# Sheet1.net
KiCad netlist of a schematic drawn in Altium Designer
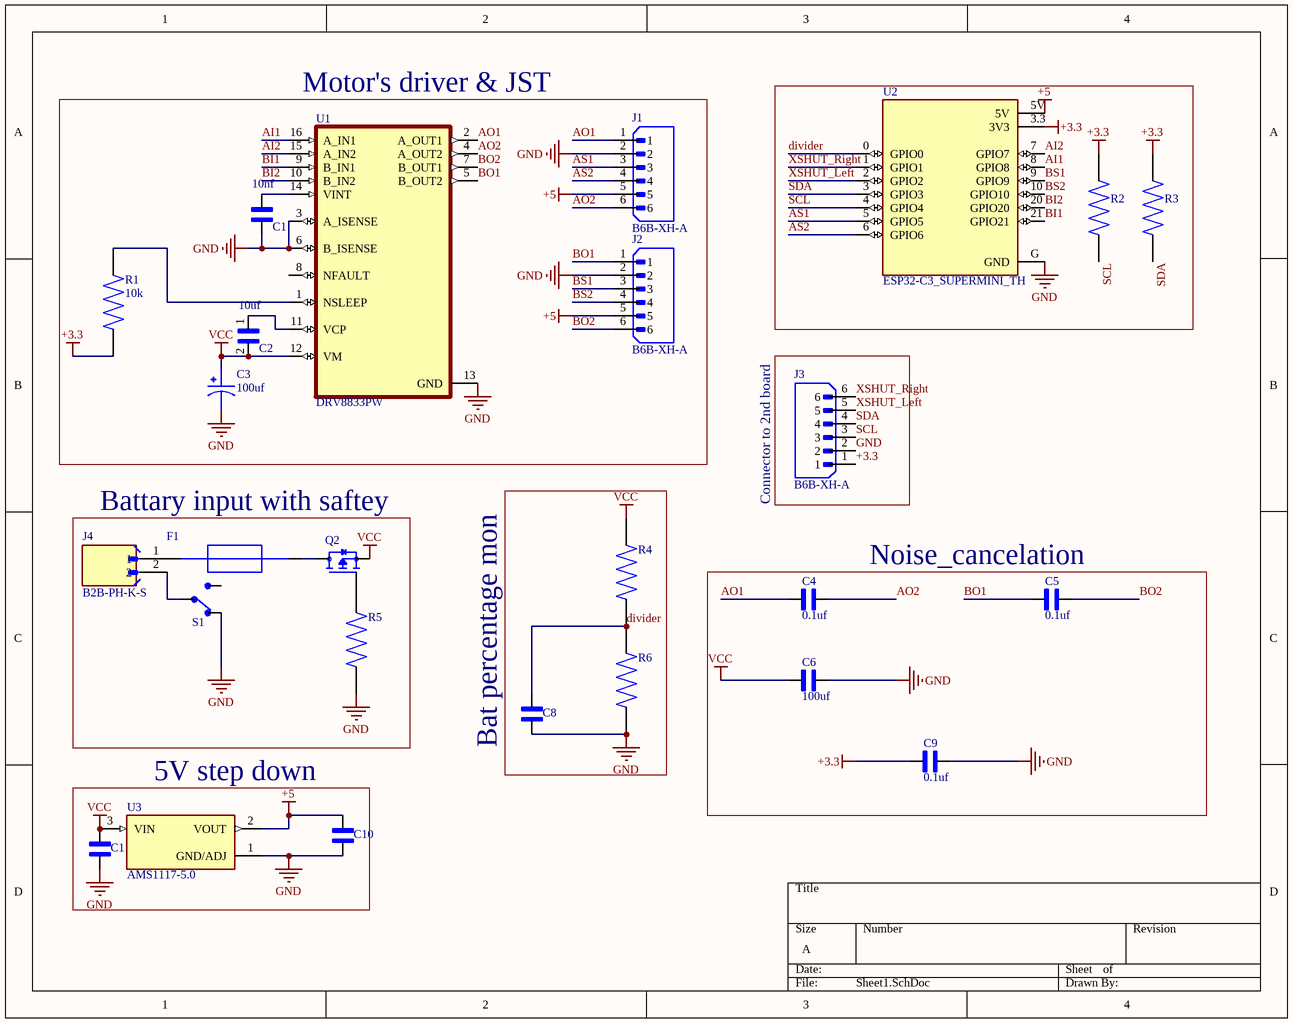
[diagram p0: Sheet1.SchDoc]

(export (version "E")
  (design (tool "Eeschema 10.0.6"))
  (components
    (comp (ref "C1")
      (value "10nf")
      (footprint "CAPC2012X88N")
      (description "0805 X7R ceramic capacitor,47nF 100V ¦ KEMET C0805C473K1RACTU")
      (fields (field (name "MF") "KEMET") (field (name "MP") "C0805C473K1RACTU"))
      (libsource (lib "Schlib1") (part "C0805C473K1RACTU"))
    )
    (comp (ref "C2")
      (value "10uf")
      (footprint "PcbLib1:CAPC3216X180N")
      (description "C Series 1206 10 nF 630 V Â±5 % Tolerance NP0 SMT Multilayer Ceramic Capacitor")
      (fields (field (name "MF") "TDK") (field (name "MP") "C3216NP02J103J160AA"))
      (libsource (lib "Schlib1") (part "C3216NP02J103J160AA"))
    )
    (comp (ref "C3")
      (value "100uf")
      (footprint "CAPMP3216X180N")
      (description "Capacitor;Tantalum;Cap 10uF;Tol 20%;SMT;Vol-Rtg 10V;Code 3216;TR ¦ AVX TAJA106M010RNJ")
      (fields (field (name "MF") "AVX") (field (name "MP") "TAJA106M010RNJ"))
      (libsource (lib "Schlib1") (part "TAJA106M010RNJ"))
    )
    (comp (ref "C4")
      (value "0.1uf")
      (footprint "CAP_ECHU1H181GX5")
      (description "Capacitor Pps Film, 180pf, 50v, 2%, 0805capacitor Pps Film, 180pf, 50v, 2%, 0805")
      (fields (field (name "MF") "Panasonic") (field (name "DIGI-KEY_PART_NUMBER") "PCF1287TR-ND"))
      (libsource (lib "Schlib1") (part "ECHU1H181GX5"))
    )
    (comp (ref "C5")
      (value "0.1uf")
      (footprint "CAP_ECHU1H181GX5")
      (description "Capacitor Pps Film, 180pf, 50v, 2%, 0805capacitor Pps Film, 180pf, 50v, 2%, 0805")
      (fields (field (name "MF") "Panasonic") (field (name "DIGI-KEY_PART_NUMBER") "PCF1287TR-ND"))
      (libsource (lib "Schlib1") (part "ECHU1H181GX5"))
    )
    (comp (ref "C6")
      (value "100uf")
      (footprint "CAPC3225X280N")
      (description "100 ÂµF Â±20% 6.3V Ceramic Capacitor X5R 1210 (3225 Metric)")
      (fields (field (name "MF") "Samsung") (field (name "MP") "CL32A107MQVNNWE"))
      (libsource (lib "Schlib1") (part "CL32A107MQVNNWE"))
    )
    (comp (ref "C8")
      (value "C0805C473K1RACTU")
      (footprint "CAPC2012X88N")
      (description "0805 X7R ceramic capacitor,47nF 100V ¦ KEMET C0805C473K1RACTU")
      (fields (field (name "MF") "KEMET"))
      (libsource (lib "Schlib1") (part "C0805C473K1RACTU"))
    )
    (comp (ref "C9")
      (value "0.1uf")
      (footprint "CAPC3225X280N")
      (description "100 ÂµF Â±20% 6.3V Ceramic Capacitor X5R 1210 (3225 Metric)")
      (fields (field (name "MF") "Samsung") (field (name "MP") "CL32A107MQVNNWE"))
      (libsource (lib "Schlib1") (part "CL32A107MQVNNWE"))
    )
    (comp (ref "C10")
      (value "C0805C473K1RACTU")
      (footprint "CAPC2012X88N")
      (description "0805 X7R ceramic capacitor,47nF 100V ¦ KEMET C0805C473K1RACTU")
      (fields (field (name "MF") "KEMET"))
      (libsource (lib "Schlib1") (part "C0805C473K1RACTU"))
    )
    (comp (ref "C11")
      (value "C0805C473K1RACTU")
      (footprint "CAPC2012X88N")
      (description "0805 X7R ceramic capacitor,47nF 100V ¦ KEMET C0805C473K1RACTU")
      (fields (field (name "MF") "KEMET"))
      (libsource (lib "") (part "C0805C473K1RACTU_1"))
    )
    (comp (ref "F1")
      (value "1206L035YR")
      (footprint "FUSC3216X75N")
      (description "Polymeric PTC Resettable Fuse 6V 350 mA Ih Surface Mount 1206 (3216 Metric), Concave")
      (fields (field (name "MF") "Littelfuse Inc."))
      (libsource (lib "Schlib1") (part "1206L035YR"))
    )
    (comp (ref "J1")
      (value "B6B-XH-A")
      (footprint "JST_B6B-XH-A")
      (fields (field (name "MF") "{'manufacturer': u'JST Sales America Inc.'}"))
      (libsource (lib "Schlib1") (part "B6B-XH-A"))
    )
    (comp (ref "J2")
      (value "B6B-XH-A")
      (footprint "JST_B6B-XH-A")
      (fields (field (name "MF") "{'manufacturer': u'JST Sales America Inc.'}"))
      (libsource (lib "Schlib1") (part "B6B-XH-A"))
    )
    (comp (ref "J3")
      (value "B6B-XH-A")
      (footprint "JST_B6B-XH-A")
      (fields (field (name "MF") "{'manufacturer': u'JST Sales America Inc.'}"))
      (libsource (lib "") (part "B6B-XH-A_1"))
    )
    (comp (ref "J4")
      (value "B2B-PH-K-S")
      (footprint "JST_B2B-PH-K-S")
      (description "Connector Header Through Hole 2 position 0.079 (2.00mm)")
      (fields (field (name "MF") "JST Sales America Inc."))
      (libsource (lib "Schlib1") (part "B2B-PH-K-S"))
    )
    (comp (ref "Q2")
      (value "IRF9540")
      (footprint "TO254P1052X465X1989-3")
      (description "P-Channel 100 V 19A (Tc) 3.7W (Ta), 150W (Tc) Surface Mount DÂ²PAK (TO-263)")
      (fields (field (name "MF") "Vishay"))
      (libsource (lib "Schlib1") (part "IRF9540"))
    )
    (comp (ref "R1")
      (value "10k")
      (footprint "RESC2012X60N")
      (description "Surface Mount Thick Film Resistor, RC Series, 39 ohm, 125 mW, - 5%, 150 V, 0805 [2012 Metric]")
      (fields (field (name "MF") "Yageo") (field (name "MP") "RC0805JR-0739RL"))
      (libsource (lib "Schlib1") (part "RC0805JR-0739RL"))
    )
    (comp (ref "R2")
      (value "RC0805JR-0739RL")
      (footprint "RESC2012X60N")
      (description "Surface Mount Thick Film Resistor, RC Series, 39 ohm, 125 mW, - 5%, 150 V, 0805 [2012 Metric]")
      (fields (field (name "MF") "Yageo"))
      (libsource (lib "Schlib1") (part "RC0805JR-0739RL"))
    )
    (comp (ref "R3")
      (value "RC0805JR-0739RL")
      (footprint "RESC2012X60N")
      (description "Surface Mount Thick Film Resistor, RC Series, 39 ohm, 125 mW, - 5%, 150 V, 0805 [2012 Metric]")
      (fields (field (name "MF") "Yageo"))
      (libsource (lib "Schlib1") (part "RC0805JR-0739RL"))
    )
    (comp (ref "R4")
      (value "RC0805JR-0739RL")
      (footprint "RESC2012X60N")
      (description "Surface Mount Thick Film Resistor, RC Series, 39 ohm, 125 mW, - 5%, 150 V, 0805 [2012 Metric]")
      (fields (field (name "MF") "Yageo"))
      (libsource (lib "Schlib1") (part "RC0805JR-0739RL"))
    )
    (comp (ref "R5")
      (value "RC0805JR-0739RL")
      (footprint "RESC2012X60N")
      (description "Surface Mount Thick Film Resistor, RC Series, 39 ohm, 125 mW, - 5%, 150 V, 0805 [2012 Metric]")
      (fields (field (name "MF") "Yageo"))
      (libsource (lib "Schlib1") (part "RC0805JR-0739RL"))
    )
    (comp (ref "R6")
      (value "RC0805JR-0739RL")
      (footprint "RESC2012X60N")
      (description "Surface Mount Thick Film Resistor, RC Series, 39 ohm, 125 mW, - 5%, 150 V, 0805 [2012 Metric]")
      (fields (field (name "MF") "Yageo"))
      (libsource (lib "Schlib1") (part "RC0805JR-0739RL"))
    )
    (comp (ref "S1")
      (value "1101M2S3CQE2")
      (footprint "SW_1101M2S3CQE2")
      (description "Switch,Slide,Sealed,SPDT,ON-NONE-ON,PC Mnt,.200 Blk Act,6A,120VAC,PC Thru-Hole ¦ C&K 1101M2S3CQE2")
      (fields (field (name "MF") "C&K"))
      (libsource (lib "Schlib1") (part "1101M2S3CQE2"))
    )
    (comp (ref "U1")
      (value "DRV8833PW")
      (footprint "SOP65P640X120-16N")
      (description "10.8-V, 2-A dual H-bridge motor driver with current regulation")
      (fields (field (name "MF") "Texas Instruments"))
      (libsource (lib "Schlib1") (part "DRV8833PW"))
    )
    (comp (ref "U2")
      (value "ESP32-C3_SUPERMINI_TH")
      (footprint "MODULE_ESP32-C3_SUPERMINI_TH")
      (description "Super tiny ESP32-C3 board")
      (fields (field (name "MF") "Espressif Systems") (field (name "MP") "ESP32-C3 SuperMini_TH"))
      (libsource (lib "Schlib1") (part "ESP32-C3_SUPERMINI_TH"))
    )
    (comp (ref "U3")
      (value "AMS1117-5.0")
      (footprint "SOT229P700X180-4N")
      (description "1A LOW DROPOUT VOLTAGE REGULATOR")
      (fields (field (name "MF") "ams"))
      (libsource (lib "Schlib1") (part "AMS1117-5.0"))
    )
  )
  (nets
    (net (code "1") (name "+3.3") (class "Default")
      (node (ref "C9") (pin "1") (pinfunction "1_1") (pintype "passive"))
      (node (ref "J3") (pin "1") (pinfunction "1_1") (pintype "passive"))
      (node (ref "R1") (pin "1") (pinfunction "1_1") (pintype "passive"))
      (node (ref "R2") (pin "1") (pinfunction "1_1") (pintype "passive"))
      (node (ref "R3") (pin "1") (pinfunction "1_1") (pintype "passive"))
      (node (ref "U2") (pin "3.3") (pinfunction "3V3_3.3") (pintype "power_in"))
    )
    (net (code "2") (name "+5") (class "Default")
      (node (ref "C10") (pin "1") (pinfunction "1_1") (pintype "passive"))
      (node (ref "J1") (pin "5") (pinfunction "5_5") (pintype "passive"))
      (node (ref "J2") (pin "5") (pinfunction "5_5") (pintype "passive"))
      (node (ref "U2") (pin "5V") (pinfunction "5V_5V") (pintype "power_in"))
      (node (ref "U3") (pin "2") (pinfunction "VOUT_2") (pintype "output"))
    )
    (net (code "3") (name "/AI1") (class "Default")
      (node (ref "U1") (pin "16") (pinfunction "A_IN1_16") (pintype "input"))
      (node (ref "U2") (pin "8") (pinfunction "GPIO8_8") (pintype "bidirectional"))
    )
    (net (code "4") (name "/AI2") (class "Default")
      (node (ref "U1") (pin "15") (pinfunction "A_IN2_15") (pintype "input"))
      (node (ref "U2") (pin "7") (pinfunction "GPIO7_7") (pintype "bidirectional"))
    )
    (net (code "5") (name "/AO1") (class "Default")
      (node (ref "C4") (pin "2") (pinfunction "2_2") (pintype "passive"))
      (node (ref "J1") (pin "1") (pinfunction "1_1") (pintype "passive"))
      (node (ref "U1") (pin "2") (pinfunction "A_OUT1_2") (pintype "output"))
    )
    (net (code "6") (name "/AO2") (class "Default")
      (node (ref "C4") (pin "1") (pinfunction "1_1") (pintype "passive"))
      (node (ref "J1") (pin "6") (pinfunction "6_6") (pintype "passive"))
      (node (ref "U1") (pin "4") (pinfunction "A_OUT2_4") (pintype "output"))
    )
    (net (code "7") (name "/AS1") (class "Default")
      (node (ref "J1") (pin "3") (pinfunction "3_3") (pintype "passive"))
      (node (ref "U2") (pin "5") (pinfunction "GPIO5_5") (pintype "bidirectional"))
    )
    (net (code "8") (name "/AS2") (class "Default")
      (node (ref "J1") (pin "4") (pinfunction "4_4") (pintype "passive"))
      (node (ref "U2") (pin "6") (pinfunction "GPIO6_6") (pintype "bidirectional"))
    )
    (net (code "9") (name "/BI1") (class "Default")
      (node (ref "U1") (pin "9") (pinfunction "B_IN1_9") (pintype "input"))
      (node (ref "U2") (pin "21") (pinfunction "GPIO21_21") (pintype "bidirectional"))
    )
    (net (code "10") (name "/BI2") (class "Default")
      (node (ref "U1") (pin "10") (pinfunction "B_IN2_10") (pintype "input"))
      (node (ref "U2") (pin "20") (pinfunction "GPIO20_20") (pintype "bidirectional"))
    )
    (net (code "11") (name "/BO1") (class "Default")
      (node (ref "C5") (pin "2") (pinfunction "2_2") (pintype "passive"))
      (node (ref "J2") (pin "1") (pinfunction "1_1") (pintype "passive"))
      (node (ref "U1") (pin "5") (pinfunction "B_OUT2_5") (pintype "output"))
    )
    (net (code "12") (name "/BO2") (class "Default")
      (node (ref "C5") (pin "1") (pinfunction "1_1") (pintype "passive"))
      (node (ref "J2") (pin "6") (pinfunction "6_6") (pintype "passive"))
      (node (ref "U1") (pin "7") (pinfunction "B_OUT1_7") (pintype "output"))
    )
    (net (code "13") (name "/BS1") (class "Default")
      (node (ref "J2") (pin "3") (pinfunction "3_3") (pintype "passive"))
      (node (ref "U2") (pin "9") (pinfunction "GPIO9_9") (pintype "bidirectional"))
    )
    (net (code "14") (name "/BS2") (class "Default")
      (node (ref "J2") (pin "4") (pinfunction "4_4") (pintype "passive"))
      (node (ref "U2") (pin "10") (pinfunction "GPIO10_10") (pintype "bidirectional"))
    )
    (net (code "15") (name "/SCL") (class "Default")
      (node (ref "J3") (pin "3") (pinfunction "3_3") (pintype "passive"))
      (node (ref "R2") (pin "2") (pinfunction "2_2") (pintype "passive"))
      (node (ref "U2") (pin "4") (pinfunction "GPIO4_4") (pintype "bidirectional"))
    )
    (net (code "16") (name "/SDA") (class "Default")
      (node (ref "J3") (pin "4") (pinfunction "4_4") (pintype "passive"))
      (node (ref "R3") (pin "2") (pinfunction "2_2") (pintype "passive"))
      (node (ref "U2") (pin "3") (pinfunction "GPIO3_3") (pintype "bidirectional"))
    )
    (net (code "17") (name "/XSHUT_Left") (class "Default")
      (node (ref "J3") (pin "5") (pinfunction "5_5") (pintype "passive"))
      (node (ref "U2") (pin "2") (pinfunction "GPIO2_2") (pintype "bidirectional"))
    )
    (net (code "18") (name "/XSHUT_Right") (class "Default")
      (node (ref "J3") (pin "6") (pinfunction "6_6") (pintype "passive"))
      (node (ref "U2") (pin "1") (pinfunction "GPIO1_1") (pintype "bidirectional"))
    )
    (net (code "19") (name "/divider") (class "Default")
      (node (ref "C8") (pin "1") (pinfunction "1_1") (pintype "passive"))
      (node (ref "R4") (pin "1") (pinfunction "1_1") (pintype "passive"))
      (node (ref "R6") (pin "2") (pinfunction "2_2") (pintype "passive"))
      (node (ref "U2") (pin "0") (pinfunction "GPIO0_0") (pintype "bidirectional"))
    )
    (net (code "20") (name "GND") (class "Default")
      (node (ref "C1") (pin "2") (pinfunction "2_2") (pintype "passive"))
      (node (ref "C10") (pin "2") (pinfunction "2_2") (pintype "passive"))
      (node (ref "C11") (pin "1") (pinfunction "1_1") (pintype "passive"))
      (node (ref "C3") (pin "2") (pinfunction "2_2") (pintype "passive"))
      (node (ref "C6") (pin "2") (pinfunction "2_2") (pintype "passive"))
      (node (ref "C8") (pin "2") (pinfunction "2_2") (pintype "passive"))
      (node (ref "C9") (pin "2") (pinfunction "2_2") (pintype "passive"))
      (node (ref "J1") (pin "2") (pinfunction "2_2") (pintype "passive"))
      (node (ref "J2") (pin "2") (pinfunction "2_2") (pintype "passive"))
      (node (ref "J3") (pin "2") (pinfunction "2_2") (pintype "passive"))
      (node (ref "R5") (pin "1") (pinfunction "1_1") (pintype "passive"))
      (node (ref "R6") (pin "1") (pinfunction "1_1") (pintype "passive"))
      (node (ref "S1") (pin "1") (pinfunction "1_1") (pintype "passive"))
      (node (ref "U1") (pin "13") (pinfunction "GND_13") (pintype "power_in"))
      (node (ref "U1") (pin "3") (pinfunction "A_ISENSE_3") (pintype "bidirectional"))
      (node (ref "U1") (pin "6") (pinfunction "B_ISENSE_6") (pintype "bidirectional"))
      (node (ref "U2") (pin "G") (pinfunction "GND_G") (pintype "power_in"))
      (node (ref "U3") (pin "1") (pinfunction "GND/ADJ_1") (pintype "power_in"))
    )
    (net (code "21") (name "Net-(F1-Pad1)") (class "Default")
      (node (ref "F1") (pin "1") (pinfunction "1_1") (pintype "passive"))
      (node (ref "J4") (pin "1") (pinfunction "1_1") (pintype "passive"))
    )
    (net (code "22") (name "Net-(J4-Pad2)") (class "Default")
      (node (ref "J4") (pin "2") (pinfunction "2_2") (pintype "passive"))
      (node (ref "S1") (pin "2") (pinfunction "2_2") (pintype "passive"))
    )
    (net (code "23") (name "Net-(Q2-D)") (class "Default")
      (node (ref "F1") (pin "2") (pinfunction "2_2") (pintype "passive"))
      (node (ref "Q2") (pin "2") (pinfunction "D_2") (pintype "passive"))
    )
    (net (code "24") (name "Net-(Q2-G)") (class "Default")
      (node (ref "Q2") (pin "1") (pinfunction "G_1") (pintype "passive"))
      (node (ref "R5") (pin "2") (pinfunction "2_2") (pintype "passive"))
    )
    (net (code "25") (name "Net-(U1-NSLEEP)") (class "Default")
      (node (ref "R1") (pin "2") (pinfunction "2_2") (pintype "passive"))
      (node (ref "U1") (pin "1") (pinfunction "NSLEEP_1") (pintype "bidirectional"))
    )
    (net (code "26") (name "Net-(U1-VCP)") (class "Default")
      (node (ref "C2") (pin "1") (pinfunction "1_1") (pintype "passive"))
      (node (ref "U1") (pin "11") (pinfunction "VCP_11") (pintype "bidirectional"))
    )
    (net (code "27") (name "Net-(U1-VINT)") (class "Default")
      (node (ref "C1") (pin "1") (pinfunction "1_1") (pintype "passive"))
      (node (ref "U1") (pin "14") (pinfunction "VINT_14") (pintype "input"))
    )
    (net (code "28") (name "VCC") (class "Default")
      (node (ref "C11") (pin "2") (pinfunction "2_2") (pintype "passive"))
      (node (ref "C2") (pin "2") (pinfunction "2_2") (pintype "passive"))
      (node (ref "C3") (pin "1") (pinfunction "1_1") (pintype "passive"))
      (node (ref "C6") (pin "1") (pinfunction "1_1") (pintype "passive"))
      (node (ref "Q2") (pin "3") (pinfunction "S_3") (pintype "passive"))
      (node (ref "R4") (pin "2") (pinfunction "2_2") (pintype "passive"))
      (node (ref "U1") (pin "12") (pinfunction "VM_12") (pintype "bidirectional"))
      (node (ref "U3") (pin "3") (pinfunction "VIN_3") (pintype "input"))
    )
    (net (code "29") (name "unconnected-(S1-Pad3)") (class "Default")
      (node (ref "S1") (pin "3") (pinfunction "3_3") (pintype "passive"))
    )
    (net (code "30") (name "unconnected-(U1-NFAULT-Pad8)") (class "Default")
      (node (ref "U1") (pin "8") (pinfunction "NFAULT_8") (pintype "bidirectional"))
    )
  )
)
